# BHOnOfreDevBoard.net
KiCad netlist of a schematic drawn in EAGLE
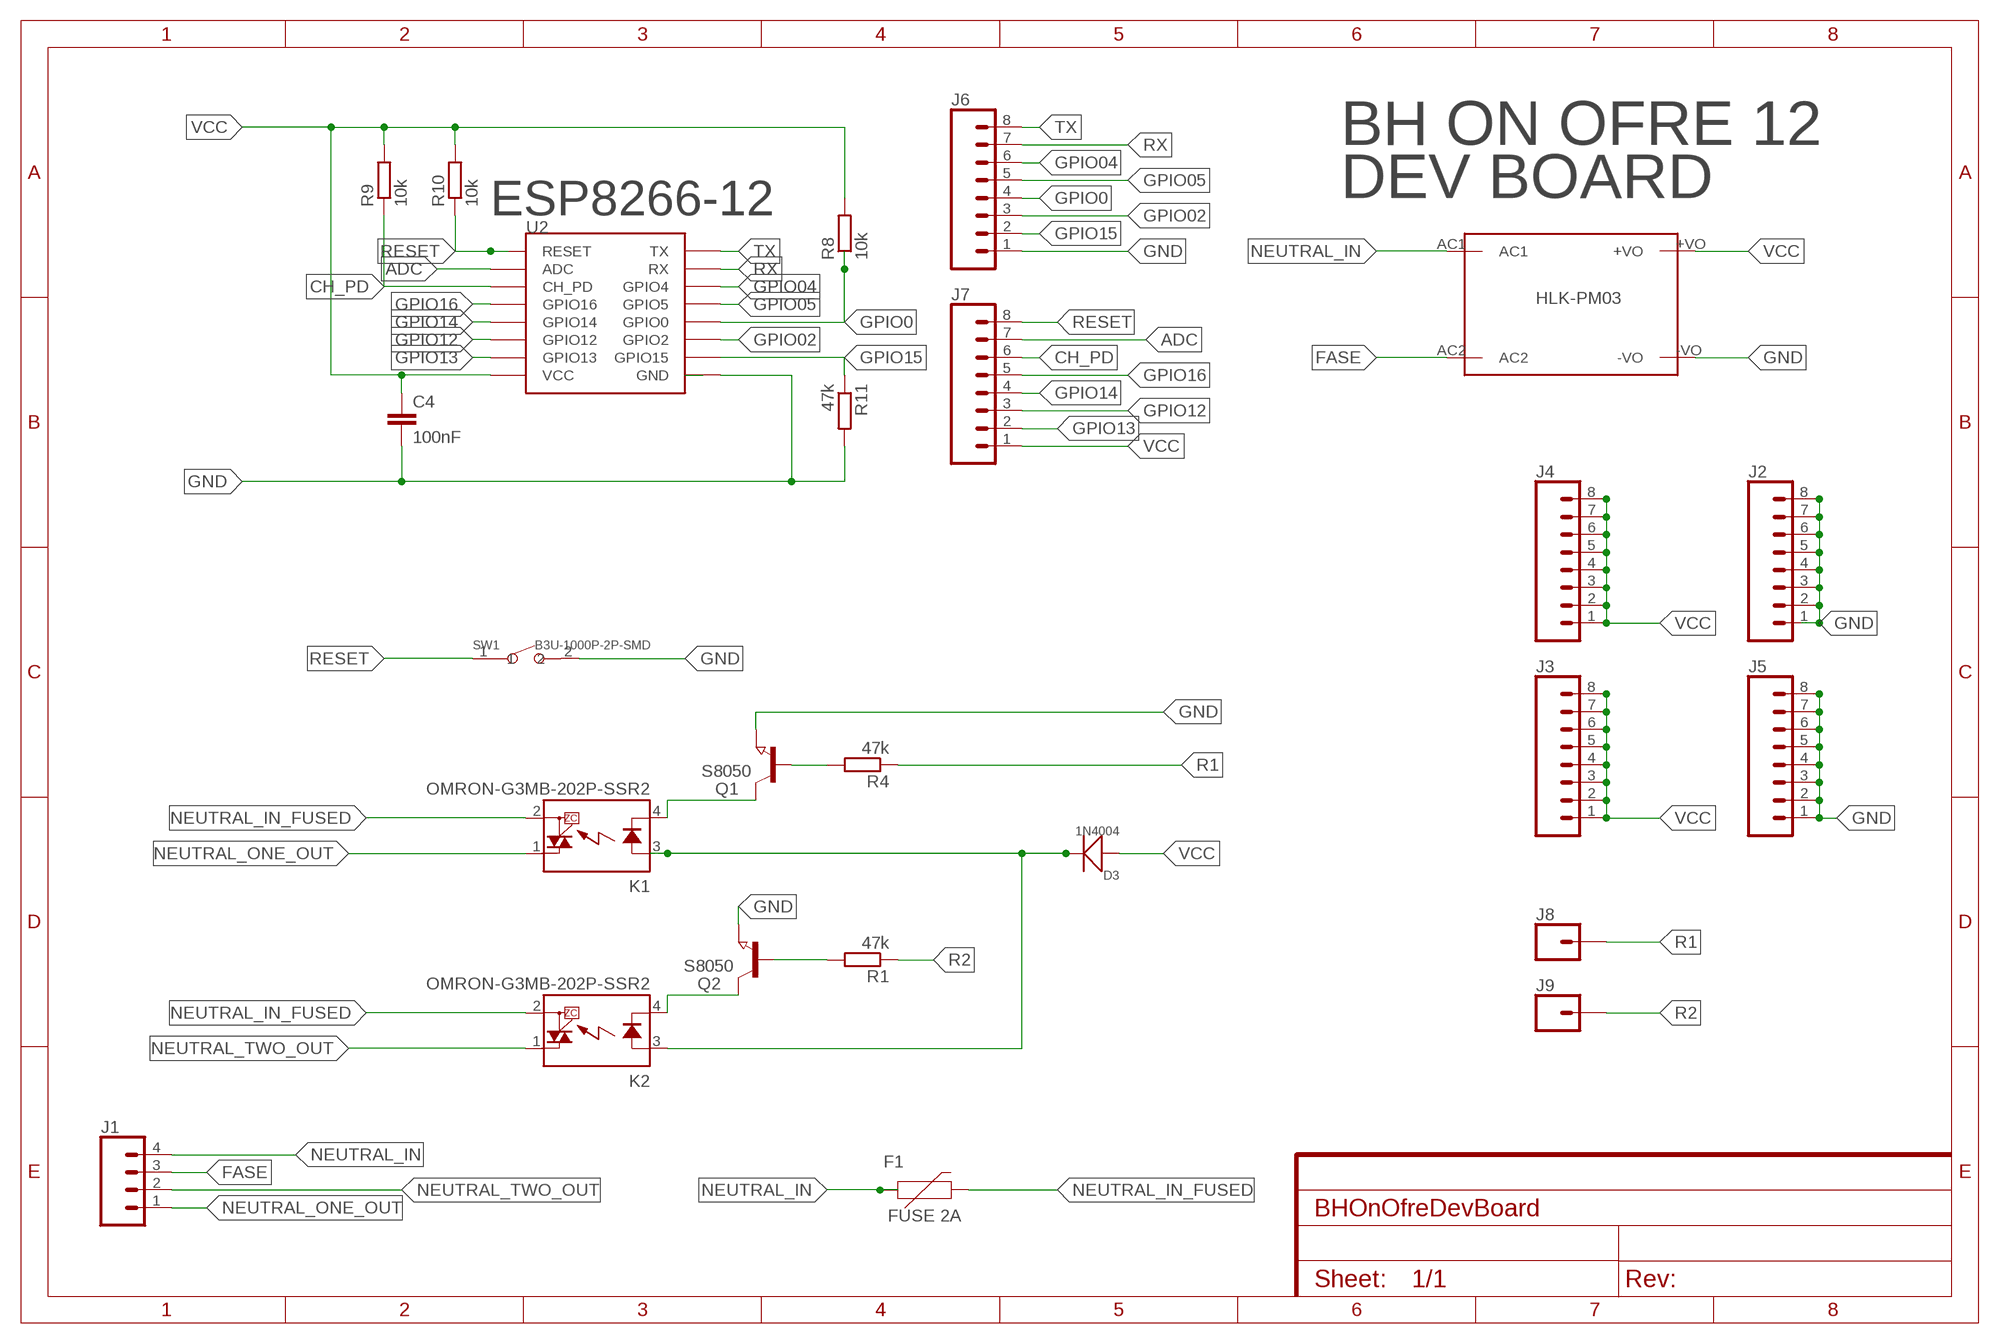
[diagram p0: schematic, sheet 1]

(export (version "E")
  (design (tool "Eeschema 10.0.6"))
  (components
    (comp (ref "C4")
      (value "100nF")
      (footprint "eagle-import:0603")
      (libsource (lib "eagle-import") (part "10NF-0603-50V-10%"))
    )
    (comp (ref "D3")
      (value "1N4004")
      (footprint "eagle-import:DO-214AC")
      (fields (field (name "MPN") "1N4007"))
      (libsource (lib "eagle-import") (part "DIODE-GEN-PURPOSE-1KV-1A(DO-214AC)"))
    )
    (comp (ref "F1")
      (value "FUSE 2A")
      (footprint "eagle-import:PTH")
      (libsource (lib "eagle-import") (part "PPTC_PTH"))
    )
    (comp (ref "J1")
      (value "CONN_04SCREW")
      (footprint "eagle-import:SCREWTERMINAL-3.5MM-4")
      (libsource (lib "eagle-import") (part "CONN_04SCREW"))
    )
    (comp (ref "J2")
      (value "CONN_08\"")
      (footprint "eagle-import:1X08")
      (libsource (lib "eagle-import") (part "CONN_08{dblquote}"))
    )
    (comp (ref "J3")
      (value "CONN_08\"")
      (footprint "eagle-import:1X08")
      (libsource (lib "eagle-import") (part "CONN_08{dblquote}"))
    )
    (comp (ref "J4")
      (value "CONN_08\"")
      (footprint "eagle-import:1X08")
      (libsource (lib "eagle-import") (part "CONN_08{dblquote}"))
    )
    (comp (ref "J5")
      (value "CONN_08\"")
      (footprint "eagle-import:1X08")
      (libsource (lib "eagle-import") (part "CONN_08{dblquote}"))
    )
    (comp (ref "J6")
      (value "CONN_08\"")
      (footprint "eagle-import:1X08")
      (libsource (lib "eagle-import") (part "CONN_08{dblquote}"))
    )
    (comp (ref "J7")
      (value "CONN_08\"")
      (footprint "eagle-import:1X08")
      (libsource (lib "eagle-import") (part "CONN_08{dblquote}"))
    )
    (comp (ref "J8")
      (value "CONN_01")
      (footprint "eagle-import:1X01")
      (libsource (lib "eagle-import") (part "CONN_01"))
    )
    (comp (ref "J9")
      (value "CONN_01")
      (footprint "eagle-import:1X01")
      (libsource (lib "eagle-import") (part "CONN_01"))
    )
    (comp (ref "K1")
      (value "OMRON-G3MB-202P-SSR2")
      (footprint "eagle-import:OMRON-G3MB-202P-SSR")
      (fields (field (name "MPN") "S202S02F"))
      (libsource (lib "eagle-import") (part "OMRON-G3MB-202P-SSR2"))
    )
    (comp (ref "K2")
      (value "OMRON-G3MB-202P-SSR2")
      (footprint "eagle-import:OMRON-G3MB-202P-SSR")
      (fields (field (name "MPN") "S202S02F"))
      (libsource (lib "eagle-import") (part "OMRON-G3MB-202P-SSR2"))
    )
    (comp (ref "Q1")
      (value "S8050")
      (footprint "eagle-import:SOT23")
      (libsource (lib "eagle-import") (part "NPN-TRANSISTOR_SOT23"))
    )
    (comp (ref "Q2")
      (value "S8050")
      (footprint "eagle-import:SOT23")
      (libsource (lib "eagle-import") (part "NPN-TRANSISTOR_SOT23"))
    )
    (comp (ref "R1")
      (value "47k")
      (footprint "eagle-import:R0603")
      (libsource (lib "eagle-import") (part "R-EU_R0603"))
    )
    (comp (ref "R4")
      (value "47k")
      (footprint "eagle-import:R0603")
      (libsource (lib "eagle-import") (part "R-EU_R0603"))
    )
    (comp (ref "R8")
      (value "10k")
      (footprint "eagle-import:R0603")
      (libsource (lib "eagle-import") (part "R-EU_R0603"))
    )
    (comp (ref "R9")
      (value "10k")
      (footprint "eagle-import:R0603")
      (libsource (lib "eagle-import") (part "R-EU_R0603"))
    )
    (comp (ref "R10")
      (value "10k")
      (footprint "eagle-import:R0603")
      (libsource (lib "eagle-import") (part "R-EU_R0603"))
    )
    (comp (ref "R11")
      (value "47k")
      (footprint "eagle-import:R0603")
      (libsource (lib "eagle-import") (part "R-EU_R0603"))
    )
    (comp (ref "SW1")
      (value "B3U-1000P-2P-SMD")
      (footprint "eagle-import:SW2-2.6-3.0X2.5X1.2+0.4MM")
      (libsource (lib "eagle-import") (part "SMD-BUTTON(2P-3.0X2.5X1.2+0.4MM)-B3U-1000P-2P-SMD"))
    )
    (comp (ref "U$2")
      (value "HLK-PM03")
      (footprint "eagle-import:HLK-PM03")
      (libsource (lib "eagle-import") (part "HLK-PM03"))
    )
    (comp (ref "U2")
      (value "ESP12SMD")
      (footprint "eagle-import:ESP12-SMD")
      (libsource (lib "eagle-import") (part "ESP12SMD"))
    )
  )
  (nets
    (net (code "1") (name "ADC") (class "Default")
      (node (ref "J7") (pin "7") (pinfunction "7_7") (pintype "passive"))
      (node (ref "U2") (pin "ADC") (pinfunction "ADC_ADC") (pintype "bidirectional"))
    )
    (net (code "2") (name "CH_PD") (class "Default")
      (node (ref "J7") (pin "6") (pinfunction "6_6") (pintype "passive"))
      (node (ref "R9") (pin "1") (pinfunction "1_1") (pintype "passive"))
      (node (ref "U2") (pin "CH_PD") (pinfunction "CH_PD_CH_PD") (pintype "bidirectional"))
    )
    (net (code "3") (name "FASE") (class "Default")
      (node (ref "J1") (pin "3") (pinfunction "3_3") (pintype "passive"))
      (node (ref "U$2") (pin "AC2") (pinfunction "AC2_AC2") (pintype "bidirectional"))
    )
    (net (code "4") (name "GND") (class "Default")
      (node (ref "C4") (pin "2") (pinfunction "2_2") (pintype "passive"))
      (node (ref "J2") (pin "1") (pinfunction "1_1") (pintype "passive"))
      (node (ref "J2") (pin "2") (pinfunction "2_2") (pintype "passive"))
      (node (ref "J2") (pin "3") (pinfunction "3_3") (pintype "passive"))
      (node (ref "J2") (pin "4") (pinfunction "4_4") (pintype "passive"))
      (node (ref "J2") (pin "5") (pinfunction "5_5") (pintype "passive"))
      (node (ref "J2") (pin "6") (pinfunction "6_6") (pintype "passive"))
      (node (ref "J2") (pin "7") (pinfunction "7_7") (pintype "passive"))
      (node (ref "J2") (pin "8") (pinfunction "8_8") (pintype "passive"))
      (node (ref "J5") (pin "1") (pinfunction "1_1") (pintype "passive"))
      (node (ref "J5") (pin "2") (pinfunction "2_2") (pintype "passive"))
      (node (ref "J5") (pin "3") (pinfunction "3_3") (pintype "passive"))
      (node (ref "J5") (pin "4") (pinfunction "4_4") (pintype "passive"))
      (node (ref "J5") (pin "5") (pinfunction "5_5") (pintype "passive"))
      (node (ref "J5") (pin "6") (pinfunction "6_6") (pintype "passive"))
      (node (ref "J5") (pin "7") (pinfunction "7_7") (pintype "passive"))
      (node (ref "J5") (pin "8") (pinfunction "8_8") (pintype "passive"))
      (node (ref "J6") (pin "1") (pinfunction "1_1") (pintype "passive"))
      (node (ref "Q1") (pin "2") (pinfunction "E_2") (pintype "passive"))
      (node (ref "Q2") (pin "2") (pinfunction "E_2") (pintype "passive"))
      (node (ref "R11") (pin "2") (pinfunction "2_2") (pintype "passive"))
      (node (ref "SW1") (pin "2") (pinfunction "2_2") (pintype "bidirectional"))
      (node (ref "U$2") (pin "-VO") (pinfunction "-VO_-VO") (pintype "bidirectional"))
      (node (ref "U2") (pin "GND") (pinfunction "GND_GND") (pintype "bidirectional"))
    )
    (net (code "5") (name "GPIO0") (class "Default")
      (node (ref "J6") (pin "4") (pinfunction "4_4") (pintype "passive"))
      (node (ref "R8") (pin "1") (pinfunction "1_1") (pintype "passive"))
      (node (ref "U2") (pin "GPIO0") (pinfunction "GPIO0_GPIO0") (pintype "bidirectional"))
    )
    (net (code "6") (name "GPIO02") (class "Default")
      (node (ref "J6") (pin "3") (pinfunction "3_3") (pintype "passive"))
      (node (ref "U2") (pin "GPIO2") (pinfunction "GPIO2_GPIO2") (pintype "bidirectional"))
    )
    (net (code "7") (name "GPIO04") (class "Default")
      (node (ref "J6") (pin "6") (pinfunction "6_6") (pintype "passive"))
      (node (ref "U2") (pin "GPIO4") (pinfunction "GPIO4_GPIO4") (pintype "bidirectional"))
    )
    (net (code "8") (name "GPIO05") (class "Default")
      (node (ref "J6") (pin "5") (pinfunction "5_5") (pintype "passive"))
      (node (ref "U2") (pin "GPIO5") (pinfunction "GPIO5_GPIO5") (pintype "bidirectional"))
    )
    (net (code "9") (name "GPIO12") (class "Default")
      (node (ref "J7") (pin "3") (pinfunction "3_3") (pintype "passive"))
      (node (ref "U2") (pin "GPIO12") (pinfunction "GPIO12_GPIO12") (pintype "bidirectional"))
    )
    (net (code "10") (name "GPIO13") (class "Default")
      (node (ref "J7") (pin "2") (pinfunction "2_2") (pintype "passive"))
      (node (ref "U2") (pin "GPIO13") (pinfunction "GPIO13_GPIO13") (pintype "bidirectional"))
    )
    (net (code "11") (name "GPIO14") (class "Default")
      (node (ref "J7") (pin "4") (pinfunction "4_4") (pintype "passive"))
      (node (ref "U2") (pin "GPIO14") (pinfunction "GPIO14_GPIO14") (pintype "bidirectional"))
    )
    (net (code "12") (name "GPIO15") (class "Default")
      (node (ref "J6") (pin "2") (pinfunction "2_2") (pintype "passive"))
      (node (ref "R11") (pin "1") (pinfunction "1_1") (pintype "passive"))
      (node (ref "U2") (pin "GPIO15") (pinfunction "GPIO15_GPIO15") (pintype "bidirectional"))
    )
    (net (code "13") (name "GPIO16") (class "Default")
      (node (ref "J7") (pin "5") (pinfunction "5_5") (pintype "passive"))
      (node (ref "U2") (pin "GPIO16") (pinfunction "GPIO16_GPIO16") (pintype "bidirectional"))
    )
    (net (code "14") (name "NEUTRAL_IN") (class "Default")
      (node (ref "F1") (pin "P$1") (pinfunction "1_P$1") (pintype "bidirectional"))
      (node (ref "J1") (pin "4") (pinfunction "4_4") (pintype "passive"))
      (node (ref "U$2") (pin "AC1") (pinfunction "AC1_AC1") (pintype "bidirectional"))
    )
    (net (code "15") (name "NEUTRAL_IN_FUSED") (class "Default")
      (node (ref "F1") (pin "P$2") (pinfunction "2_P$2") (pintype "bidirectional"))
      (node (ref "K1") (pin "2") (pinfunction "DS2_2") (pintype "passive"))
      (node (ref "K2") (pin "2") (pinfunction "DS2_2") (pintype "passive"))
    )
    (net (code "16") (name "NEUTRAL_ONE_OUT") (class "Default")
      (node (ref "J1") (pin "1") (pinfunction "1_1") (pintype "passive"))
      (node (ref "K1") (pin "1") (pinfunction "DS1_1") (pintype "passive"))
    )
    (net (code "17") (name "NEUTRAL_TWO_OUT") (class "Default")
      (node (ref "J1") (pin "2") (pinfunction "2_2") (pintype "passive"))
      (node (ref "K2") (pin "1") (pinfunction "DS1_1") (pintype "passive"))
    )
    (net (code "18") (name "Net-(D3--)") (class "Default")
      (node (ref "D3") (pin "2") (pinfunction "-_2") (pintype "passive"))
      (node (ref "K1") (pin "3") (pinfunction "A_3") (pintype "passive"))
      (node (ref "K2") (pin "3") (pinfunction "A_3") (pintype "passive"))
    )
    (net (code "19") (name "Net-(K1-K)") (class "Default")
      (node (ref "K1") (pin "4") (pinfunction "K_4") (pintype "passive"))
      (node (ref "Q1") (pin "3") (pinfunction "C_3") (pintype "passive"))
    )
    (net (code "20") (name "Net-(K2-K)") (class "Default")
      (node (ref "K2") (pin "4") (pinfunction "K_4") (pintype "passive"))
      (node (ref "Q2") (pin "3") (pinfunction "C_3") (pintype "passive"))
    )
    (net (code "21") (name "Net-(Q1-B)") (class "Default")
      (node (ref "Q1") (pin "1") (pinfunction "B_1") (pintype "passive"))
      (node (ref "R4") (pin "2") (pinfunction "2_2") (pintype "passive"))
    )
    (net (code "22") (name "Net-(Q2-B)") (class "Default")
      (node (ref "Q2") (pin "1") (pinfunction "B_1") (pintype "passive"))
      (node (ref "R1") (pin "2") (pinfunction "2_2") (pintype "passive"))
    )
    (net (code "23") (name "R1") (class "Default")
      (node (ref "J8") (pin "1") (pinfunction "1_1") (pintype "passive"))
      (node (ref "R4") (pin "1") (pinfunction "1_1") (pintype "passive"))
    )
    (net (code "24") (name "R2") (class "Default")
      (node (ref "J9") (pin "1") (pinfunction "1_1") (pintype "passive"))
      (node (ref "R1") (pin "1") (pinfunction "1_1") (pintype "passive"))
    )
    (net (code "25") (name "RESET") (class "Default")
      (node (ref "J7") (pin "8") (pinfunction "8_8") (pintype "passive"))
      (node (ref "R10") (pin "1") (pinfunction "1_1") (pintype "passive"))
      (node (ref "SW1") (pin "1") (pinfunction "1_1") (pintype "bidirectional"))
      (node (ref "U2") (pin "RESET") (pinfunction "RESET_RESET") (pintype "bidirectional"))
    )
    (net (code "26") (name "RX") (class "Default")
      (node (ref "J6") (pin "7") (pinfunction "7_7") (pintype "passive"))
      (node (ref "U2") (pin "RXD0") (pinfunction "RX_RXD0") (pintype "bidirectional"))
    )
    (net (code "27") (name "TX") (class "Default")
      (node (ref "J6") (pin "8") (pinfunction "8_8") (pintype "passive"))
      (node (ref "U2") (pin "TXD0") (pinfunction "TX_TXD0") (pintype "bidirectional"))
    )
    (net (code "28") (name "VCC") (class "Default")
      (node (ref "C4") (pin "1") (pinfunction "1_1") (pintype "passive"))
      (node (ref "D3") (pin "1") (pinfunction "+_1") (pintype "passive"))
      (node (ref "J3") (pin "1") (pinfunction "1_1") (pintype "passive"))
      (node (ref "J3") (pin "2") (pinfunction "2_2") (pintype "passive"))
      (node (ref "J3") (pin "3") (pinfunction "3_3") (pintype "passive"))
      (node (ref "J3") (pin "4") (pinfunction "4_4") (pintype "passive"))
      (node (ref "J3") (pin "5") (pinfunction "5_5") (pintype "passive"))
      (node (ref "J3") (pin "6") (pinfunction "6_6") (pintype "passive"))
      (node (ref "J3") (pin "7") (pinfunction "7_7") (pintype "passive"))
      (node (ref "J3") (pin "8") (pinfunction "8_8") (pintype "passive"))
      (node (ref "J4") (pin "1") (pinfunction "1_1") (pintype "passive"))
      (node (ref "J4") (pin "2") (pinfunction "2_2") (pintype "passive"))
      (node (ref "J4") (pin "3") (pinfunction "3_3") (pintype "passive"))
      (node (ref "J4") (pin "4") (pinfunction "4_4") (pintype "passive"))
      (node (ref "J4") (pin "5") (pinfunction "5_5") (pintype "passive"))
      (node (ref "J4") (pin "6") (pinfunction "6_6") (pintype "passive"))
      (node (ref "J4") (pin "7") (pinfunction "7_7") (pintype "passive"))
      (node (ref "J4") (pin "8") (pinfunction "8_8") (pintype "passive"))
      (node (ref "J7") (pin "1") (pinfunction "1_1") (pintype "passive"))
      (node (ref "R10") (pin "2") (pinfunction "2_2") (pintype "passive"))
      (node (ref "R8") (pin "2") (pinfunction "2_2") (pintype "passive"))
      (node (ref "R9") (pin "2") (pinfunction "2_2") (pintype "passive"))
      (node (ref "U$2") (pin "+VO") (pinfunction "+VO_+VO") (pintype "bidirectional"))
      (node (ref "U2") (pin "VCC") (pinfunction "VCC_VCC") (pintype "bidirectional"))
    )
  )
)
